# jetson_agx_breakout.net
KiCad netlist of a schematic drawn in Altium Designer
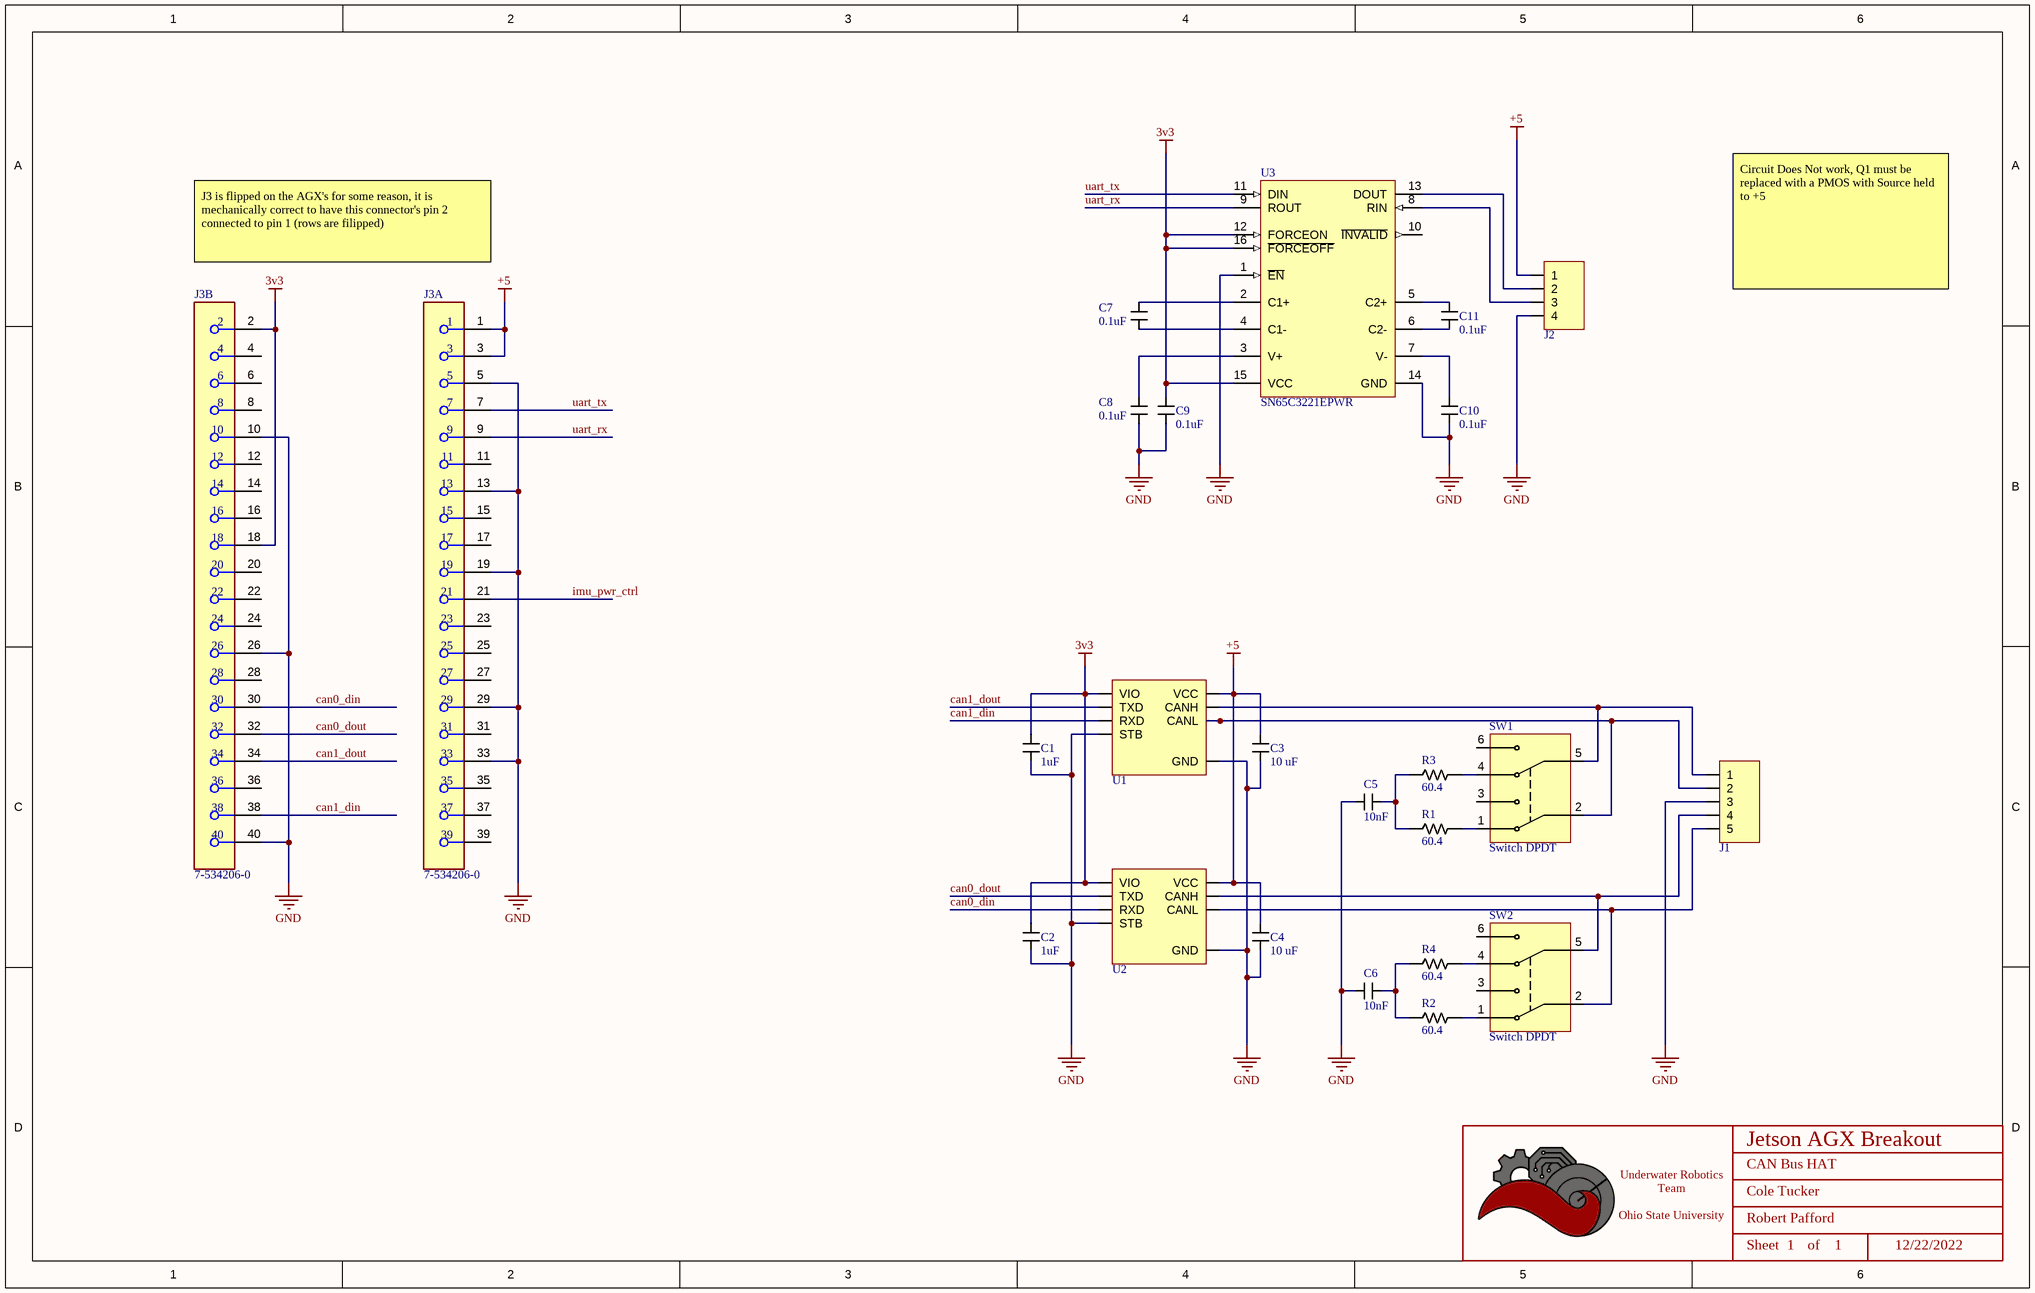
[diagram p0: jetson_agx_breakout.SchDoc]

(export (version "E")
  (design (tool "Eeschema 10.0.6"))
  (components
    (comp (ref "*")
      (value "Title_Block")
      (footprint "LOGO")
      (description "UWRT Schematic Title Block Template\r\n\r\nCreated June 2021, Dylan Trainor")
      (libsource (lib "UWRT") (part "Title_Block"))
    )
    (comp (ref "C1")
      (value "1uF")
      (footprint "CAPACITOR_0603")
      (description "Cap 1uF 16V +/-10%\r\nCeramic 0603")
      (fields
        (field (name "TOLERANCE") "+/- 10%")
        (field (name "VOLTAGE") "16V")
        (field (name "MADE BY") "Flip B")
      )
      (libsource (lib "Capacitors") (part "CAPACITOR_1uF_0603"))
    )
    (comp (ref "C2")
      (value "1uF")
      (footprint "CAPACITOR_0603")
      (description "Cap 1uF 16V +/-10%\r\nCeramic 0603")
      (fields
        (field (name "TOLERANCE") "+/- 10%")
        (field (name "VOLTAGE") "16V")
        (field (name "MADE BY") "Flip B")
      )
      (libsource (lib "Capacitors") (part "CAPACITOR_1uF_0603"))
    )
    (comp (ref "C3")
      (value "10uF Ceramic 6.3V")
      (footprint "CAPACITOR_0603")
      (description "Cap 10uF 6.3V +/-20%\r\nCeramic 0603")
      (fields
        (field (name "TOLERANCE") "+/- 20%")
        (field (name "VOLTAGE") "6.3V")
        (field (name "VALUE (UF)") "10 uF")
        (field (name "MADE BY") "Flip B")
      )
      (libsource (lib "Capacitors") (part "CAPACITOR_10uF_0603"))
    )
    (comp (ref "C4")
      (value "10uF Ceramic 6.3V")
      (footprint "CAPACITOR_0603")
      (description "Cap 10uF 6.3V +/-20%\r\nCeramic 0603")
      (fields
        (field (name "TOLERANCE") "+/- 20%")
        (field (name "VOLTAGE") "6.3V")
        (field (name "VALUE (UF)") "10 uF")
        (field (name "MADE BY") "Flip B")
      )
      (libsource (lib "Capacitors") (part "CAPACITOR_10uF_0603"))
    )
    (comp (ref "C5")
      (value "10nF")
      (footprint "CAPACITOR_0603")
      (description "Cap 10nF 6.3V +/-20%\r\nCeramic 0603")
      (fields
        (field (name "TOLERANCE") "+/- 10%")
        (field (name "VOLTAGE") "6.3V")
        (field (name "MADE BY") "Flip B")
      )
      (libsource (lib "Capacitors") (part "CAPACITOR_0.01uF_0603"))
    )
    (comp (ref "C6")
      (value "10nF")
      (footprint "CAPACITOR_0603")
      (description "Cap 10nF 6.3V +/-20%\r\nCeramic 0603")
      (fields
        (field (name "TOLERANCE") "+/- 10%")
        (field (name "VOLTAGE") "6.3V")
        (field (name "MADE BY") "Flip B")
      )
      (libsource (lib "Capacitors") (part "CAPACITOR_0.01uF_0603"))
    )
    (comp (ref "C7")
      (value "0.1uF")
      (footprint "CAPACITOR_0603")
      (description "Cap 100nF 6.3V +/-10%\r\nCeramic 0603")
      (fields
        (field (name "TOLERANCE") "+/- 10%")
        (field (name "VOLTAGE") "6.3V")
        (field (name "MADE BY") "Flip B")
      )
      (libsource (lib "Capacitors") (part "CAPACITOR_0.1uF_0603"))
    )
    (comp (ref "C8")
      (value "0.1uF")
      (footprint "CAPACITOR_0603")
      (description "Cap 100nF 6.3V +/-10%\r\nCeramic 0603")
      (fields
        (field (name "TOLERANCE") "+/- 10%")
        (field (name "VOLTAGE") "6.3V")
        (field (name "MADE BY") "Flip B")
      )
      (libsource (lib "Capacitors") (part "CAPACITOR_0.1uF_0603"))
    )
    (comp (ref "C9")
      (value "0.1uF")
      (footprint "CAPACITOR_0603")
      (description "Cap 100nF 6.3V +/-10%\r\nCeramic 0603")
      (fields
        (field (name "TOLERANCE") "+/- 10%")
        (field (name "VOLTAGE") "6.3V")
        (field (name "MADE BY") "Flip B")
      )
      (libsource (lib "Capacitors") (part "CAPACITOR_0.1uF_0603"))
    )
    (comp (ref "C10")
      (value "0.1uF")
      (footprint "CAPACITOR_0603")
      (description "Cap 100nF 6.3V +/-10%\r\nCeramic 0603")
      (fields
        (field (name "TOLERANCE") "+/- 10%")
        (field (name "VOLTAGE") "6.3V")
        (field (name "MADE BY") "Flip B")
      )
      (libsource (lib "Capacitors") (part "CAPACITOR_0.1uF_0603"))
    )
    (comp (ref "C11")
      (value "0.1uF")
      (footprint "CAPACITOR_0603")
      (description "Cap 100nF 6.3V +/-10%\r\nCeramic 0603")
      (fields
        (field (name "TOLERANCE") "+/- 10%")
        (field (name "VOLTAGE") "6.3V")
        (field (name "MADE BY") "Flip B")
      )
      (libsource (lib "Capacitors") (part "CAPACITOR_0.1uF_0603"))
    )
    (comp (ref "J1")
      (value "XH2.54 VERT")
      (footprint "CONN_JST_XH254_5POS_VERT")
      (description "JST XH 2.54mm Pitch 5 Pos Vertical")
      (fields (field (name "MANUFACTURER") "JST") (field (name "CREATED BY") "Robert P"))
      (libsource (lib "Connectors") (part "CONN_JST_XH254_5POS_VERT"))
    )
    (comp (ref "J2")
      (value "XH2.54 VERT")
      (footprint "CONN_JST_XH254_4POS_VERT")
      (description "JST XH 2.54mm Pitch 4 Pos Vertical")
      (fields (field (name "MANUFACTURER") "JST") (field (name "CREATED BY") "Robert P"))
      (libsource (lib "Connectors") (part "CONN_JST_XH254_4POS_VERT"))
    )
    (comp (ref "J3")
      (value "7-534206-0")
      (footprint "FP-7-534206-0-MFG")
      (description "CONN RCPT 40POS 0.1 GOLD PCB")
      (fields
        (field (name "MANUFACTURER") "TE Connectivity")
        (field (name "OCTOPART") "https://octopart.com/7-534206-0-te+connectivity-39516831")
      )
      (libsource (lib "Altium Content Vault") (part "7acf1c4a8db21028d11741a46a6ec78"))
    )
    (comp (ref "R1")
      (value "60.4 Ohm 1% 1/16W")
      (footprint "RESISTOR_0402")
      (description "RES 60.4 OHM 1% 1/16W 0402")
      (fields
        (field (name "TOLERANCE") "+/- 1%")
        (field (name "VALUE  (OHMS)") "60.4")
        (field (name "MADE BY") "Robert Pafford")
      )
      (libsource (lib "Resistors") (part "RESISTOR_60.4_0402"))
    )
    (comp (ref "R2")
      (value "60.4 Ohm 1% 1/16W")
      (footprint "RESISTOR_0402")
      (description "RES 60.4 OHM 1% 1/16W 0402")
      (fields
        (field (name "TOLERANCE") "+/- 1%")
        (field (name "VALUE  (OHMS)") "60.4")
        (field (name "MADE BY") "Robert Pafford")
      )
      (libsource (lib "Resistors") (part "RESISTOR_60.4_0402"))
    )
    (comp (ref "R3")
      (value "60.4 Ohm 1% 1/16W")
      (footprint "RESISTOR_0402")
      (description "RES 60.4 OHM 1% 1/16W 0402")
      (fields
        (field (name "TOLERANCE") "+/- 1%")
        (field (name "VALUE  (OHMS)") "60.4")
        (field (name "MADE BY") "Robert Pafford")
      )
      (libsource (lib "Resistors") (part "RESISTOR_60.4_0402"))
    )
    (comp (ref "R4")
      (value "60.4 Ohm 1% 1/16W")
      (footprint "RESISTOR_0402")
      (description "RES 60.4 OHM 1% 1/16W 0402")
      (fields
        (field (name "TOLERANCE") "+/- 1%")
        (field (name "VALUE  (OHMS)") "60.4")
        (field (name "MADE BY") "Robert Pafford")
      )
      (libsource (lib "Resistors") (part "RESISTOR_60.4_0402"))
    )
    (comp (ref "SW1")
      (value "Switch DPDT")
      (footprint "CAS-220TA")
      (description "GOLD SWITCH FLUSH SLIDE DPDT 100MA 6V")
      (fields (field (name "MADE BY") "Robert Pafford"))
      (libsource (lib "Switches") (part "CAS-220TA_CAN_TERM"))
    )
    (comp (ref "SW2")
      (value "Switch DPDT")
      (footprint "CAS-220TA")
      (description "GOLD SWITCH FLUSH SLIDE DPDT 100MA 6V")
      (fields (field (name "MADE BY") "Robert Pafford"))
      (libsource (lib "Switches") (part "CAS-220TA_CAN_TERM"))
    )
    (comp (ref "U1")
      (value "CAN Transceiver")
      (footprint "SOIC-8")
      (description "CAN Interface IC High-Speed CAN Transceiver with Standby Mode")
      (fields (field (name "MADE BY") "Robert Pafford"))
      (libsource (lib "Integrated Circuits") (part "TJA1442AT"))
    )
    (comp (ref "U2")
      (value "CAN Transceiver")
      (footprint "SOIC-8")
      (description "CAN Interface IC High-Speed CAN Transceiver with Standby Mode")
      (fields (field (name "MADE BY") "Robert Pafford"))
      (libsource (lib "Integrated Circuits") (part "TJA1442AT"))
    )
    (comp (ref "U3")
      (value "SN65C3221EPWR")
      (footprint "PW0016A_M")
      (libsource (lib "Altium Content Vault") (part "TI-SN65C3221E-TSSOP_PW-16"))
    )
  )
  (nets
    (net (code "1") (name "+5") (class "Default")
      (node (ref "C3") (pin "1") (pinfunction "1_1") (pintype "passive"))
      (node (ref "C4") (pin "1") (pinfunction "1_1") (pintype "passive"))
      (node (ref "J2") (pin "1") (pinfunction "1_1") (pintype "passive"))
      (node (ref "J3") (pin "1") (pinfunction "1_1") (pintype "passive"))
      (node (ref "J3") (pin "3") (pinfunction "3_3") (pintype "passive"))
      (node (ref "U1") (pin "3") (pinfunction "VCC_3") (pintype "passive"))
      (node (ref "U2") (pin "3") (pinfunction "VCC_3") (pintype "passive"))
    )
    (net (code "2") (name "/can0_din") (class "Default")
      (node (ref "J3") (pin "30") (pinfunction "30_30") (pintype "passive"))
      (node (ref "U2") (pin "4") (pinfunction "RXD_4") (pintype "passive"))
    )
    (net (code "3") (name "/can0_dout") (class "Default")
      (node (ref "J3") (pin "32") (pinfunction "32_32") (pintype "passive"))
      (node (ref "U2") (pin "1") (pinfunction "TXD_1") (pintype "passive"))
    )
    (net (code "4") (name "/can1_din") (class "Default")
      (node (ref "J3") (pin "38") (pinfunction "38_38") (pintype "passive"))
      (node (ref "U1") (pin "4") (pinfunction "RXD_4") (pintype "passive"))
    )
    (net (code "5") (name "/can1_dout") (class "Default")
      (node (ref "J3") (pin "34") (pinfunction "34_34") (pintype "passive"))
      (node (ref "U1") (pin "1") (pinfunction "TXD_1") (pintype "passive"))
    )
    (net (code "6") (name "/imu_pwr_ctrl") (class "Default")
      (node (ref "J3") (pin "21") (pinfunction "21_21") (pintype "passive"))
    )
    (net (code "7") (name "/uart_rx") (class "Default")
      (node (ref "J3") (pin "9") (pinfunction "9_9") (pintype "passive"))
      (node (ref "U3") (pin "9") (pinfunction "ROUT_9") (pintype "tri_state"))
    )
    (net (code "8") (name "/uart_tx") (class "Default")
      (node (ref "J3") (pin "7") (pinfunction "7_7") (pintype "passive"))
      (node (ref "U3") (pin "11") (pinfunction "DIN_11") (pintype "input"))
    )
    (net (code "9") (name "3v3") (class "Default")
      (node (ref "C1") (pin "1") (pinfunction "1_1") (pintype "passive"))
      (node (ref "C2") (pin "1") (pinfunction "1_1") (pintype "passive"))
      (node (ref "C9") (pin "1") (pinfunction "1_1") (pintype "passive"))
      (node (ref "J3") (pin "18") (pinfunction "18_18") (pintype "passive"))
      (node (ref "J3") (pin "2") (pinfunction "2_2") (pintype "passive"))
      (node (ref "U1") (pin "5") (pinfunction "VIO_5") (pintype "passive"))
      (node (ref "U2") (pin "5") (pinfunction "VIO_5") (pintype "passive"))
      (node (ref "U3") (pin "12") (pinfunction "FORCEON_12") (pintype "input"))
      (node (ref "U3") (pin "15") (pinfunction "VCC_15") (pintype "power_in"))
      (node (ref "U3") (pin "16") (pinfunction "~{FORCEOFF}_16") (pintype "input"))
    )
    (net (code "10") (name "GND") (class "Default")
      (node (ref "C1") (pin "2") (pinfunction "2_2") (pintype "passive"))
      (node (ref "C10") (pin "2") (pinfunction "2_2") (pintype "passive"))
      (node (ref "C2") (pin "2") (pinfunction "2_2") (pintype "passive"))
      (node (ref "C3") (pin "2") (pinfunction "2_2") (pintype "passive"))
      (node (ref "C4") (pin "2") (pinfunction "2_2") (pintype "passive"))
      (node (ref "C5") (pin "1") (pinfunction "1_1") (pintype "passive"))
      (node (ref "C6") (pin "1") (pinfunction "1_1") (pintype "passive"))
      (node (ref "C8") (pin "2") (pinfunction "2_2") (pintype "passive"))
      (node (ref "C9") (pin "2") (pinfunction "2_2") (pintype "passive"))
      (node (ref "J1") (pin "3") (pinfunction "3_3") (pintype "passive"))
      (node (ref "J2") (pin "4") (pinfunction "4_4") (pintype "passive"))
      (node (ref "J3") (pin "10") (pinfunction "10_10") (pintype "passive"))
      (node (ref "J3") (pin "13") (pinfunction "13_13") (pintype "passive"))
      (node (ref "J3") (pin "19") (pinfunction "19_19") (pintype "passive"))
      (node (ref "J3") (pin "26") (pinfunction "26_26") (pintype "passive"))
      (node (ref "J3") (pin "29") (pinfunction "29_29") (pintype "passive"))
      (node (ref "J3") (pin "33") (pinfunction "33_33") (pintype "passive"))
      (node (ref "J3") (pin "40") (pinfunction "40_40") (pintype "passive"))
      (node (ref "J3") (pin "5") (pinfunction "5_5") (pintype "passive"))
      (node (ref "U1") (pin "2") (pinfunction "GND_2") (pintype "passive"))
      (node (ref "U1") (pin "8") (pinfunction "STB_8") (pintype "passive"))
      (node (ref "U2") (pin "2") (pinfunction "GND_2") (pintype "passive"))
      (node (ref "U2") (pin "8") (pinfunction "STB_8") (pintype "passive"))
      (node (ref "U3") (pin "1") (pinfunction "~{EN}_1") (pintype "input"))
      (node (ref "U3") (pin "14") (pinfunction "GND_14") (pintype "power_in"))
    )
    (net (code "11") (name "Net-(C5-Pad2)") (class "Default")
      (node (ref "C5") (pin "2") (pinfunction "2_2") (pintype "passive"))
      (node (ref "R1") (pin "2") (pinfunction "2_2") (pintype "passive"))
      (node (ref "R3") (pin "2") (pinfunction "2_2") (pintype "passive"))
    )
    (net (code "12") (name "Net-(C6-Pad2)") (class "Default")
      (node (ref "C6") (pin "2") (pinfunction "2_2") (pintype "passive"))
      (node (ref "R2") (pin "2") (pinfunction "2_2") (pintype "passive"))
      (node (ref "R4") (pin "2") (pinfunction "2_2") (pintype "passive"))
    )
    (net (code "13") (name "Net-(R1-Pad1)") (class "Default")
      (node (ref "R1") (pin "1") (pinfunction "1_1") (pintype "passive"))
      (node (ref "SW1") (pin "1") (pintype "passive"))
    )
    (net (code "14") (name "Net-(R2-Pad1)") (class "Default")
      (node (ref "R2") (pin "1") (pinfunction "1_1") (pintype "passive"))
      (node (ref "SW2") (pin "1") (pintype "passive"))
    )
    (net (code "15") (name "Net-(R3-Pad1)") (class "Default")
      (node (ref "R3") (pin "1") (pinfunction "1_1") (pintype "passive"))
      (node (ref "SW1") (pin "4") (pintype "passive"))
    )
    (net (code "16") (name "Net-(R4-Pad1)") (class "Default")
      (node (ref "R4") (pin "1") (pinfunction "1_1") (pintype "passive"))
      (node (ref "SW2") (pin "4") (pintype "passive"))
    )
    (net (code "17") (name "Net-(U1-CANH)") (class "Default")
      (node (ref "J1") (pin "1") (pinfunction "1_1") (pintype "passive"))
      (node (ref "SW1") (pin "5") (pintype "passive"))
      (node (ref "U1") (pin "7") (pinfunction "CANH_7") (pintype "passive"))
    )
    (net (code "18") (name "Net-(U1-CANL)") (class "Default")
      (node (ref "J1") (pin "2") (pinfunction "2_2") (pintype "passive"))
      (node (ref "SW1") (pin "2") (pintype "passive"))
      (node (ref "U1") (pin "6") (pinfunction "CANL_6") (pintype "passive"))
    )
    (net (code "19") (name "Net-(U2-CANH)") (class "Default")
      (node (ref "J1") (pin "4") (pinfunction "4_4") (pintype "passive"))
      (node (ref "SW2") (pin "5") (pintype "passive"))
      (node (ref "U2") (pin "7") (pinfunction "CANH_7") (pintype "passive"))
    )
    (net (code "20") (name "Net-(U2-CANL)") (class "Default")
      (node (ref "J1") (pin "5") (pinfunction "5_5") (pintype "passive"))
      (node (ref "SW2") (pin "2") (pintype "passive"))
      (node (ref "U2") (pin "6") (pinfunction "CANL_6") (pintype "passive"))
    )
    (net (code "21") (name "Net-(U3-C1+)") (class "Default")
      (node (ref "C7") (pin "1") (pinfunction "1_1") (pintype "passive"))
      (node (ref "U3") (pin "2") (pinfunction "C1+_2") (pintype "passive"))
    )
    (net (code "22") (name "Net-(U3-C1-)") (class "Default")
      (node (ref "C7") (pin "2") (pinfunction "2_2") (pintype "passive"))
      (node (ref "U3") (pin "4") (pinfunction "C1-_4") (pintype "passive"))
    )
    (net (code "23") (name "Net-(U3-C2+)") (class "Default")
      (node (ref "C11") (pin "1") (pinfunction "1_1") (pintype "passive"))
      (node (ref "U3") (pin "5") (pinfunction "C2+_5") (pintype "passive"))
    )
    (net (code "24") (name "Net-(U3-C2-)") (class "Default")
      (node (ref "C11") (pin "2") (pinfunction "2_2") (pintype "passive"))
      (node (ref "U3") (pin "6") (pinfunction "C2-_6") (pintype "passive"))
    )
    (net (code "25") (name "Net-(U3-DOUT)") (class "Default")
      (node (ref "J2") (pin "2") (pinfunction "2_2") (pintype "passive"))
      (node (ref "U3") (pin "13") (pinfunction "DOUT_13") (pintype "tri_state"))
    )
    (net (code "26") (name "Net-(U3-RIN)") (class "Default")
      (node (ref "J2") (pin "3") (pinfunction "3_3") (pintype "passive"))
      (node (ref "U3") (pin "8") (pinfunction "RIN_8") (pintype "input"))
    )
    (net (code "27") (name "Net-(U3-V+)") (class "Default")
      (node (ref "C8") (pin "1") (pinfunction "1_1") (pintype "passive"))
      (node (ref "U3") (pin "3") (pinfunction "V+_3") (pintype "power_in"))
    )
    (net (code "28") (name "Net-(U3-V-)") (class "Default")
      (node (ref "C10") (pin "1") (pinfunction "1_1") (pintype "passive"))
      (node (ref "U3") (pin "7") (pinfunction "V-_7") (pintype "power_in"))
    )
    (net (code "29") (name "unconnected-(J3-Pad4)") (class "Default")
      (node (ref "J3") (pin "4") (pinfunction "4_4") (pintype "passive"))
    )
    (net (code "30") (name "unconnected-(J3-Pad6)") (class "Default")
      (node (ref "J3") (pin "6") (pinfunction "6_6") (pintype "passive"))
    )
    (net (code "31") (name "unconnected-(J3-Pad8)") (class "Default")
      (node (ref "J3") (pin "8") (pinfunction "8_8") (pintype "passive"))
    )
    (net (code "32") (name "unconnected-(J3-Pad11)") (class "Default")
      (node (ref "J3") (pin "11") (pinfunction "11_11") (pintype "passive"))
    )
    (net (code "33") (name "unconnected-(J3-Pad12)") (class "Default")
      (node (ref "J3") (pin "12") (pinfunction "12_12") (pintype "passive"))
    )
    (net (code "34") (name "unconnected-(J3-Pad14)") (class "Default")
      (node (ref "J3") (pin "14") (pinfunction "14_14") (pintype "passive"))
    )
    (net (code "35") (name "unconnected-(J3-Pad15)") (class "Default")
      (node (ref "J3") (pin "15") (pinfunction "15_15") (pintype "passive"))
    )
    (net (code "36") (name "unconnected-(J3-Pad16)") (class "Default")
      (node (ref "J3") (pin "16") (pinfunction "16_16") (pintype "passive"))
    )
    (net (code "37") (name "unconnected-(J3-Pad17)") (class "Default")
      (node (ref "J3") (pin "17") (pinfunction "17_17") (pintype "passive"))
    )
    (net (code "38") (name "unconnected-(J3-Pad20)") (class "Default")
      (node (ref "J3") (pin "20") (pinfunction "20_20") (pintype "passive"))
    )
    (net (code "39") (name "unconnected-(J3-Pad22)") (class "Default")
      (node (ref "J3") (pin "22") (pinfunction "22_22") (pintype "passive"))
    )
    (net (code "40") (name "unconnected-(J3-Pad23)") (class "Default")
      (node (ref "J3") (pin "23") (pinfunction "23_23") (pintype "passive"))
    )
    (net (code "41") (name "unconnected-(J3-Pad24)") (class "Default")
      (node (ref "J3") (pin "24") (pinfunction "24_24") (pintype "passive"))
    )
    (net (code "42") (name "unconnected-(J3-Pad25)") (class "Default")
      (node (ref "J3") (pin "25") (pinfunction "25_25") (pintype "passive"))
    )
    (net (code "43") (name "unconnected-(J3-Pad27)") (class "Default")
      (node (ref "J3") (pin "27") (pinfunction "27_27") (pintype "passive"))
    )
    (net (code "44") (name "unconnected-(J3-Pad28)") (class "Default")
      (node (ref "J3") (pin "28") (pinfunction "28_28") (pintype "passive"))
    )
    (net (code "45") (name "unconnected-(J3-Pad31)") (class "Default")
      (node (ref "J3") (pin "31") (pinfunction "31_31") (pintype "passive"))
    )
    (net (code "46") (name "unconnected-(J3-Pad35)") (class "Default")
      (node (ref "J3") (pin "35") (pinfunction "35_35") (pintype "passive"))
    )
    (net (code "47") (name "unconnected-(J3-Pad36)") (class "Default")
      (node (ref "J3") (pin "36") (pinfunction "36_36") (pintype "passive"))
    )
    (net (code "48") (name "unconnected-(J3-Pad37)") (class "Default")
      (node (ref "J3") (pin "37") (pinfunction "37_37") (pintype "passive"))
    )
    (net (code "49") (name "unconnected-(J3-Pad39)") (class "Default")
      (node (ref "J3") (pin "39") (pinfunction "39_39") (pintype "passive"))
    )
    (net (code "50") (name "unconnected-(SW1-Pad3)") (class "Default")
      (node (ref "SW1") (pin "3") (pintype "passive"))
    )
    (net (code "51") (name "unconnected-(SW1-Pad6)") (class "Default")
      (node (ref "SW1") (pin "6") (pintype "passive"))
    )
    (net (code "52") (name "unconnected-(SW2-Pad3)") (class "Default")
      (node (ref "SW2") (pin "3") (pintype "passive"))
    )
    (net (code "53") (name "unconnected-(SW2-Pad6)") (class "Default")
      (node (ref "SW2") (pin "6") (pintype "passive"))
    )
    (net (code "54") (name "unconnected-(U3-~{INVALID}-Pad10)") (class "Default")
      (node (ref "U3") (pin "10") (pinfunction "~{INVALID}_10") (pintype "output"))
    )
  )
)
